# DSI_LCD.net
KiCad netlist of a schematic drawn in Altium Designer
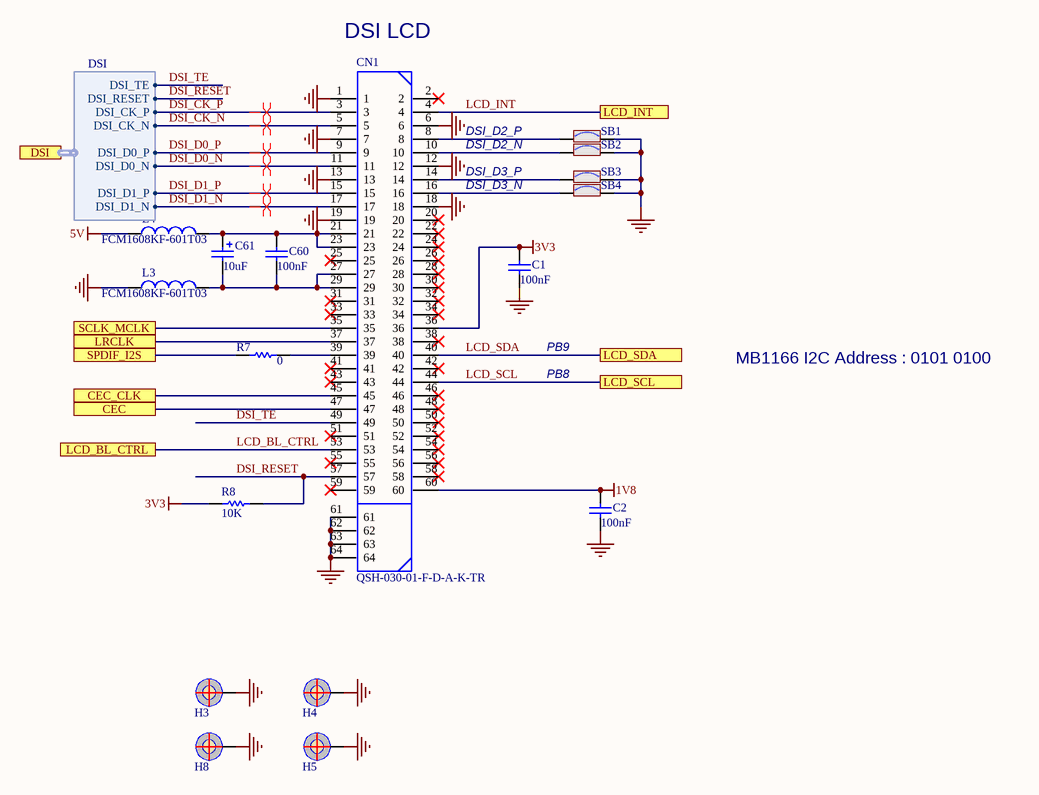
[diagram p0: DSI_LCD.SchDoc]

(export (version "E")
  (design (tool "Eeschema 10.0.6"))
  (components
    (comp (ref "C1")
      (value "100nF")
      (footprint "0603C")
      (description "Capacitor,100nF,16V,X7R,10%,0603,YAGEO")
      (libsource (lib "MCD_TOOLS_CAPACITOR") (part "Cap_100nF_X7R_10%_0603"))
    )
    (comp (ref "C2")
      (value "100nF")
      (footprint "0603C")
      (description "Capacitor,100nF,16V,X7R,10%,0603,YAGEO")
      (libsource (lib "MCD_TOOLS_CAPACITOR") (part "Cap_100nF_X7R_10%_0603"))
    )
    (comp (ref "C60")
      (value "100nF")
      (footprint "0603C")
      (description "Capacitor,100nF,16V,X7R,10%,0603,YAGEO")
      (libsource (lib "MCD_TOOLS_CAPACITOR") (part "Cap_100nF_X7R_10%_0603"))
    )
    (comp (ref "C61")
      (value "10uF")
      (footprint "TAN-A")
      (description "Polarized Capacitor,10uF,10V,10%,typeA,VISHAY")
      (libsource (lib "MCD_TOOLS_CAPACITOR") (part "Cap_10uF_POL_10%_TANA"))
    )
    (comp (ref "CN1")
      (value "QSH-030-01-F-D-A-K-TR")
      (footprint "QSH-030-01-F-D-A")
      (description "HIGH SPEED SOCKET STRIP, .5mm PITCH, 60 PINS")
      (fields (field (name "PROVIDED") "Sub Co"))
      (libsource (lib "MCD_TOOLS_CONNECTOR") (part "QSH-030-01-F-D-A"))
    )
    (comp (ref "H3")
      (value "POSITION HOLE")
      (footprint "HOLE_C9D4R5-1")
      (libsource (lib "mb1045") (part "POSITION HOLE"))
    )
    (comp (ref "H4")
      (value "POSITION HOLE")
      (footprint "HOLE_C9D4R5")
      (libsource (lib "mb1045") (part "POSITION HOLE"))
    )
    (comp (ref "H5")
      (value "POSITION HOLE")
      (footprint "HOLE_C9D4R5")
      (libsource (lib "mb1045") (part "POSITION HOLE"))
    )
    (comp (ref "H8")
      (value "POSITION HOLE")
      (footprint "HOLE_C9D4R5-1")
      (libsource (lib "mb1045") (part "POSITION HOLE"))
    )
    (comp (ref "L3")
      (value "FCM1608KF-601T03")
      (footprint "0603L")
      (description "Bead,600R,350mA,0603,FCM1608KF-601T03,Tai-tech")
      (libsource (lib "MCD_TOOLS") (part "BEAD_600R_350MA_0603"))
    )
    (comp (ref "L4")
      (value "FCM1608KF-601T03")
      (footprint "0603L")
      (description "Bead,600R,350mA,0603,FCM1608KF-601T03,Tai-tech")
      (libsource (lib "MCD_TOOLS") (part "BEAD_600R_350MA_0603"))
    )
    (comp (ref "R7")
      (value "0")
      (footprint "0402R")
      (description "Resistor,0,0402,5%,YAGEO")
      (libsource (lib "MCD_TOOLS_RESISTOR") (part "Res_0_5%_0402"))
    )
    (comp (ref "R8")
      (value "10K")
      (footprint "0402R")
      (description "Resistor,10K,0402,1%,YAGEO")
      (libsource (lib "MCD_TOOLS_RESISTOR") (part "Res_10K_1%_0402"))
    )
    (comp (ref "SB1")
      (value "Solder Bridge ON")
      (footprint "JP2_SMD")
      (libsource (lib "MCD_TOOLS_MISCELLANEOUS") (part "SB_ON"))
    )
    (comp (ref "SB2")
      (value "Solder Bridge ON")
      (footprint "JP2_SMD")
      (libsource (lib "MCD_TOOLS_MISCELLANEOUS") (part "SB_ON"))
    )
    (comp (ref "SB3")
      (value "Solder Bridge ON")
      (footprint "JP2_SMD")
      (libsource (lib "MCD_TOOLS_MISCELLANEOUS") (part "SB_ON"))
    )
    (comp (ref "SB4")
      (value "Solder Bridge ON")
      (footprint "JP2_SMD")
      (libsource (lib "MCD_TOOLS_MISCELLANEOUS") (part "SB_ON"))
    )
  )
  (nets
    (net (code "2") (name "/CEC") (class "Default")
      (node (ref "CN1") (pin "47") (pinfunction "47_47") (pintype "passive"))
    )
    (net (code "3") (name "/CEC_CLK") (class "Default")
      (node (ref "CN1") (pin "45") (pinfunction "45_45") (pintype "passive"))
    )
    (net (code "4") (name "/DSI_CK_N") (class "Default")
      (node (ref "CN1") (pin "5") (pinfunction "5_5") (pintype "passive"))
    )
    (net (code "5") (name "/DSI_CK_P") (class "Default")
      (node (ref "CN1") (pin "3") (pinfunction "3_3") (pintype "passive"))
    )
    (net (code "6") (name "/DSI_D0_N") (class "Default")
      (node (ref "CN1") (pin "11") (pinfunction "11_11") (pintype "passive"))
    )
    (net (code "7") (name "/DSI_D0_P") (class "Default")
      (node (ref "CN1") (pin "9") (pinfunction "9_9") (pintype "passive"))
    )
    (net (code "8") (name "/DSI_D1_N") (class "Default")
      (node (ref "CN1") (pin "17") (pinfunction "17_17") (pintype "passive"))
    )
    (net (code "9") (name "/DSI_D1_P") (class "Default")
      (node (ref "CN1") (pin "15") (pinfunction "15_15") (pintype "passive"))
    )
    (net (code "10") (name "/DSI_RESET") (class "Default")
      (node (ref "CN1") (pin "57") (pinfunction "57_57") (pintype "passive"))
      (node (ref "R8") (pin "2") (pinfunction "2_2") (pintype "passive"))
    )
    (net (code "11") (name "/DSI_TE") (class "Default")
      (node (ref "CN1") (pin "49") (pinfunction "49_49") (pintype "passive"))
    )
    (net (code "12") (name "/LCD_BL_CTRL") (class "Default")
      (node (ref "CN1") (pin "53") (pinfunction "53_53") (pintype "passive"))
    )
    (net (code "13") (name "/LCD_INT") (class "Default")
      (node (ref "CN1") (pin "4") (pinfunction "4_4") (pintype "passive"))
    )
    (net (code "14") (name "/LCD_SCL") (class "Default")
      (node (ref "CN1") (pin "44") (pinfunction "44_44") (pintype "passive"))
    )
    (net (code "15") (name "/LCD_SDA") (class "Default")
      (node (ref "CN1") (pin "40") (pinfunction "40_40") (pintype "passive"))
    )
    (net (code "16") (name "/LRCLK") (class "Default")
      (node (ref "CN1") (pin "37") (pinfunction "37_37") (pintype "passive"))
    )
    (net (code "17") (name "/SCLK_MCLK") (class "Default")
      (node (ref "CN1") (pin "35") (pinfunction "35_35") (pintype "passive"))
    )
    (net (code "18") (name "/SPDIF_I2S") (class "Default")
      (node (ref "R7") (pin "1") (pinfunction "1_1") (pintype "passive"))
    )
    (net (code "20") (name "1V8") (class "Default")
      (node (ref "C2") (pin "2") (pinfunction "2_2") (pintype "passive"))
      (node (ref "CN1") (pin "60") (pinfunction "60_60") (pintype "passive"))
    )
    (net (code "21") (name "3V3") (class "Default")
      (node (ref "C1") (pin "2") (pinfunction "2_2") (pintype "passive"))
      (node (ref "CN1") (pin "36") (pinfunction "36_36") (pintype "passive"))
      (node (ref "R8") (pin "1") (pinfunction "1_1") (pintype "passive"))
    )
    (net (code "22") (name "5V") (class "Default")
      (node (ref "L4") (pin "1") (pinfunction "1_1") (pintype "passive"))
    )
    (net (code "23") (name "GND") (class "Default")
      (node (ref "C1") (pin "1") (pinfunction "1_1") (pintype "passive"))
      (node (ref "C2") (pin "1") (pinfunction "1_1") (pintype "passive"))
      (node (ref "CN1") (pin "1") (pinfunction "1_1") (pintype "passive"))
      (node (ref "CN1") (pin "12") (pinfunction "12_12") (pintype "passive"))
      (node (ref "CN1") (pin "13") (pinfunction "13_13") (pintype "passive"))
      (node (ref "CN1") (pin "18") (pinfunction "18_18") (pintype "passive"))
      (node (ref "CN1") (pin "19") (pinfunction "19_19") (pintype "passive"))
      (node (ref "CN1") (pin "6") (pinfunction "6_6") (pintype "passive"))
      (node (ref "CN1") (pin "61") (pinfunction "61_61") (pintype "passive"))
      (node (ref "CN1") (pin "62") (pinfunction "62_62") (pintype "passive"))
      (node (ref "CN1") (pin "63") (pinfunction "63_63") (pintype "passive"))
      (node (ref "CN1") (pin "64") (pinfunction "64_64") (pintype "passive"))
      (node (ref "CN1") (pin "7") (pinfunction "7_7") (pintype "passive"))
      (node (ref "H3") (pin "1") (pinfunction "1_1") (pintype "passive"))
      (node (ref "H4") (pin "1") (pinfunction "1_1") (pintype "passive"))
      (node (ref "H5") (pin "1") (pinfunction "1_1") (pintype "passive"))
      (node (ref "H8") (pin "1") (pinfunction "1_1") (pintype "passive"))
      (node (ref "L3") (pin "1") (pinfunction "1_1") (pintype "passive"))
      (node (ref "SB1") (pin "2") (pinfunction "2_2") (pintype "passive"))
      (node (ref "SB2") (pin "2") (pinfunction "2_2") (pintype "passive"))
      (node (ref "SB3") (pin "2") (pinfunction "2_2") (pintype "passive"))
      (node (ref "SB4") (pin "2") (pinfunction "2_2") (pintype "passive"))
    )
    (net (code "24") (name "Net-(C60-Pad1)") (class "Default")
      (node (ref "C60") (pin "1") (pinfunction "1_1") (pintype "passive"))
      (node (ref "C61") (pin "2") (pinfunction "2_2") (pintype "passive"))
      (node (ref "CN1") (pin "27") (pinfunction "27_27") (pintype "passive"))
      (node (ref "CN1") (pin "29") (pinfunction "29_29") (pintype "passive"))
      (node (ref "L3") (pin "2") (pinfunction "2_2") (pintype "passive"))
    )
    (net (code "25") (name "Net-(C60-Pad2)") (class "Default")
      (node (ref "C60") (pin "2") (pinfunction "2_2") (pintype "passive"))
      (node (ref "C61") (pin "1") (pinfunction "1_1") (pintype "passive"))
      (node (ref "CN1") (pin "21") (pinfunction "21_21") (pintype "passive"))
      (node (ref "CN1") (pin "23") (pinfunction "23_23") (pintype "passive"))
      (node (ref "L4") (pin "2") (pinfunction "2_2") (pintype "passive"))
    )
    (net (code "26") (name "Net-(CN1-Pad8)") (class "Default")
      (node (ref "CN1") (pin "8") (pinfunction "8_8") (pintype "passive"))
      (node (ref "SB1") (pin "1") (pinfunction "1_1") (pintype "passive"))
    )
    (net (code "27") (name "Net-(CN1-Pad10)") (class "Default")
      (node (ref "CN1") (pin "10") (pinfunction "10_10") (pintype "passive"))
      (node (ref "SB2") (pin "1") (pinfunction "1_1") (pintype "passive"))
    )
    (net (code "28") (name "Net-(CN1-Pad14)") (class "Default")
      (node (ref "CN1") (pin "14") (pinfunction "14_14") (pintype "passive"))
      (node (ref "SB3") (pin "1") (pinfunction "1_1") (pintype "passive"))
    )
    (net (code "29") (name "Net-(CN1-Pad16)") (class "Default")
      (node (ref "CN1") (pin "16") (pinfunction "16_16") (pintype "passive"))
      (node (ref "SB4") (pin "1") (pinfunction "1_1") (pintype "passive"))
    )
    (net (code "30") (name "Net-(CN1-Pad39)") (class "Default")
      (node (ref "CN1") (pin "39") (pinfunction "39_39") (pintype "passive"))
      (node (ref "R7") (pin "2") (pinfunction "2_2") (pintype "passive"))
    )
    (net (code "31") (name "unconnected-(CN1-Pad2)") (class "Default")
      (node (ref "CN1") (pin "2") (pinfunction "2_2") (pintype "passive+no_connect"))
    )
    (net (code "32") (name "unconnected-(CN1-Pad20)") (class "Default")
      (node (ref "CN1") (pin "20") (pinfunction "20_20") (pintype "passive+no_connect"))
    )
    (net (code "33") (name "unconnected-(CN1-Pad22)") (class "Default")
      (node (ref "CN1") (pin "22") (pinfunction "22_22") (pintype "passive+no_connect"))
    )
    (net (code "34") (name "unconnected-(CN1-Pad24)") (class "Default")
      (node (ref "CN1") (pin "24") (pinfunction "24_24") (pintype "passive+no_connect"))
    )
    (net (code "35") (name "unconnected-(CN1-Pad25)") (class "Default")
      (node (ref "CN1") (pin "25") (pinfunction "25_25") (pintype "passive+no_connect"))
    )
    (net (code "36") (name "unconnected-(CN1-Pad26)") (class "Default")
      (node (ref "CN1") (pin "26") (pinfunction "26_26") (pintype "passive+no_connect"))
    )
    (net (code "37") (name "unconnected-(CN1-Pad28)") (class "Default")
      (node (ref "CN1") (pin "28") (pinfunction "28_28") (pintype "passive+no_connect"))
    )
    (net (code "38") (name "unconnected-(CN1-Pad30)") (class "Default")
      (node (ref "CN1") (pin "30") (pinfunction "30_30") (pintype "passive+no_connect"))
    )
    (net (code "39") (name "unconnected-(CN1-Pad31)") (class "Default")
      (node (ref "CN1") (pin "31") (pinfunction "31_31") (pintype "passive+no_connect"))
    )
    (net (code "40") (name "unconnected-(CN1-Pad32)") (class "Default")
      (node (ref "CN1") (pin "32") (pinfunction "32_32") (pintype "passive+no_connect"))
    )
    (net (code "41") (name "unconnected-(CN1-Pad33)") (class "Default")
      (node (ref "CN1") (pin "33") (pinfunction "33_33") (pintype "passive+no_connect"))
    )
    (net (code "42") (name "unconnected-(CN1-Pad34)") (class "Default")
      (node (ref "CN1") (pin "34") (pinfunction "34_34") (pintype "passive+no_connect"))
    )
    (net (code "43") (name "unconnected-(CN1-Pad38)") (class "Default")
      (node (ref "CN1") (pin "38") (pinfunction "38_38") (pintype "passive+no_connect"))
    )
    (net (code "44") (name "unconnected-(CN1-Pad41)") (class "Default")
      (node (ref "CN1") (pin "41") (pinfunction "41_41") (pintype "passive+no_connect"))
    )
    (net (code "45") (name "unconnected-(CN1-Pad42)") (class "Default")
      (node (ref "CN1") (pin "42") (pinfunction "42_42") (pintype "passive+no_connect"))
    )
    (net (code "46") (name "unconnected-(CN1-Pad43)") (class "Default")
      (node (ref "CN1") (pin "43") (pinfunction "43_43") (pintype "passive+no_connect"))
    )
    (net (code "47") (name "unconnected-(CN1-Pad46)") (class "Default")
      (node (ref "CN1") (pin "46") (pinfunction "46_46") (pintype "passive+no_connect"))
    )
    (net (code "48") (name "unconnected-(CN1-Pad48)") (class "Default")
      (node (ref "CN1") (pin "48") (pinfunction "48_48") (pintype "passive+no_connect"))
    )
    (net (code "49") (name "unconnected-(CN1-Pad50)") (class "Default")
      (node (ref "CN1") (pin "50") (pinfunction "50_50") (pintype "passive+no_connect"))
    )
    (net (code "50") (name "unconnected-(CN1-Pad51)") (class "Default")
      (node (ref "CN1") (pin "51") (pinfunction "51_51") (pintype "passive+no_connect"))
    )
    (net (code "51") (name "unconnected-(CN1-Pad52)") (class "Default")
      (node (ref "CN1") (pin "52") (pinfunction "52_52") (pintype "passive+no_connect"))
    )
    (net (code "52") (name "unconnected-(CN1-Pad54)") (class "Default")
      (node (ref "CN1") (pin "54") (pinfunction "54_54") (pintype "passive+no_connect"))
    )
    (net (code "53") (name "unconnected-(CN1-Pad55)") (class "Default")
      (node (ref "CN1") (pin "55") (pinfunction "55_55") (pintype "passive+no_connect"))
    )
    (net (code "54") (name "unconnected-(CN1-Pad56)") (class "Default")
      (node (ref "CN1") (pin "56") (pinfunction "56_56") (pintype "passive+no_connect"))
    )
    (net (code "55") (name "unconnected-(CN1-Pad58)") (class "Default")
      (node (ref "CN1") (pin "58") (pinfunction "58_58") (pintype "passive+no_connect"))
    )
    (net (code "56") (name "unconnected-(CN1-Pad59)") (class "Default")
      (node (ref "CN1") (pin "59") (pinfunction "59_59") (pintype "passive+no_connect"))
    )
  )
)
